# POWERSYSTEM.net
KiCad netlist of a schematic drawn in Altium Designer
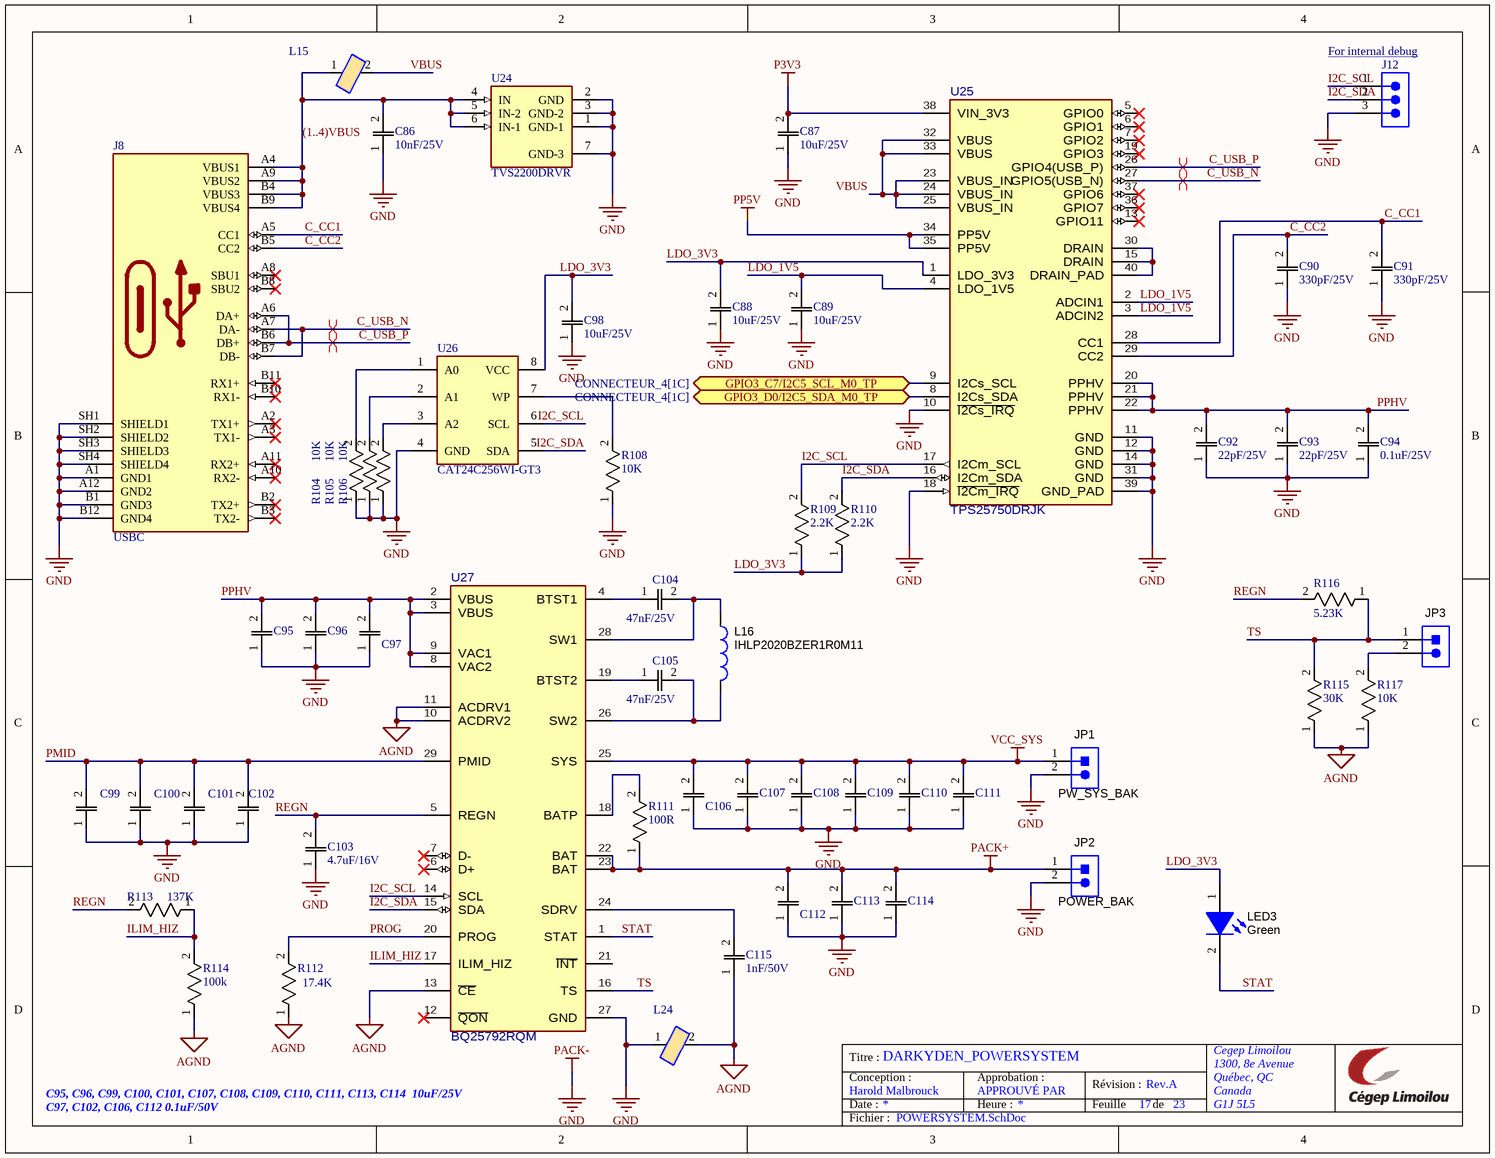
[diagram p0: POWERSYSTEM.SchDoc]

(export (version "E")
  (design (tool "Eeschema 10.0.6"))
  (components
    (comp (ref "C86")
      (value "10nF/25V")
      (footprint "C0805")
      (description "0.01uF 25V X7R 10% SMD 0805 125C Paper T/R")
      (fields
        (field (name "MANUFACTURER_PART_NUMBER") "C0805C103K3RACTU")
        (field (name "MOUSER PART NUMBER") "80-C0805C103K3R")
      )
      (libsource (lib "DARKYDEN") (part "C0805C103K3RACTU"))
    )
    (comp (ref "C87")
      (value "10uF/25V")
      (footprint "C0805")
      (description "10uF / 25 VDC, +85degC, X5R Dielec, +/-10% ¦ KEMET C0805C106K3PACTU 0805")
      (fields
        (field (name "MANUFACTURER") "KEMET")
        (field (name "MANUFACTURER PART NUMBER") "C0805C106K3PACTU")
      )
      (libsource (lib "DARKYDEN") (part "C0805C106K3PACTU"))
    )
    (comp (ref "C88")
      (value "10uF/25V")
      (footprint "C0805")
      (description "10uF / 25 VDC, +85degC, X5R Dielec, +/-10% ¦ KEMET C0805C106K3PACTU 0805")
      (fields
        (field (name "MANUFACTURER") "KEMET")
        (field (name "MANUFACTURER PART NUMBER") "C0805C106K3PACTU")
      )
      (libsource (lib "DARKYDEN") (part "C0805C106K3PACTU"))
    )
    (comp (ref "C89")
      (value "10uF/25V")
      (footprint "C0805")
      (description "10uF / 25 VDC, +85degC, X5R Dielec, +/-10% ¦ KEMET C0805C106K3PACTU 0805")
      (fields
        (field (name "MANUFACTURER") "KEMET")
        (field (name "MANUFACTURER PART NUMBER") "C0805C106K3PACTU")
      )
      (libsource (lib "DARKYDEN") (part "C0805C106K3PACTU"))
    )
    (comp (ref "C90")
      (value "330pF/25V")
      (footprint "SamacSys:C0805")
      (description "330pF 25VC0G 0805 10%")
      (fields
        (field (name "MANUFACTURER_PART_NUMBER") "C0805C331K3GACTU")
        (field (name "MOUSER PART NUMBER") "80-C0805C331K3G")
      )
      (libsource (lib "DARKYDEN") (part "C0805C331K3GACTU"))
    )
    (comp (ref "C91")
      (value "330pF/25V")
      (footprint "SamacSys:C0805")
      (description "330pF 25VC0G 0805 10%")
      (fields
        (field (name "MANUFACTURER_PART_NUMBER") "C0805C331K3GACTU")
        (field (name "MOUSER PART NUMBER") "80-C0805C331K3G")
      )
      (libsource (lib "DARKYDEN") (part "C0805C331K3GACTU"))
    )
    (comp (ref "C92")
      (value "22pF/25V")
      (footprint "c0805")
      (description "22uF/25V 20% X5R 0805")
      (fields
        (field (name "MANUFACTURER_PART_NUMBER") "CL21A226MAYNNNE")
        (field (name "MOUSER PART NUMBER") "187-CL21A226MAYNNNE")
      )
      (libsource (lib "DARKYDEN") (part "CL21A226MAYNNNE"))
    )
    (comp (ref "C93")
      (value "22pF/25V")
      (footprint "c0805")
      (description "22uF/25V 20% X5R 0805")
      (fields
        (field (name "MANUFACTURER_PART_NUMBER") "CL21A226MAYNNNE")
        (field (name "MOUSER PART NUMBER") "187-CL21A226MAYNNNE")
      )
      (libsource (lib "DARKYDEN") (part "CL21A226MAYNNNE"))
    )
    (comp (ref "C94")
      (value "0.1uF/25V")
      (footprint "c0805")
      (description "0.1uF 25V X7R 10% SMD 0805 125C Plastic T/R")
      (fields
        (field (name "MANUFACTURER") "KEMET")
        (field (name "MANUFACTURER PART NUMBER") "C0805C104K3RACTU")
      )
      (libsource (lib "DARKYDEN") (part "C0805C104K3RACTU"))
    )
    (comp (ref "C95")
      (value "10uF/25V")
      (footprint "C0805")
      (description "10uF / 25 VDC, +85degC, X5R Dielec, +/-10% ¦ KEMET C0805C106K3PACTU 0805")
      (fields
        (field (name "MANUFACTURER") "KEMET")
        (field (name "MANUFACTURER PART NUMBER") "C0805C106K3PACTU")
      )
      (libsource (lib "DARKYDEN") (part "C0805C106K3PACTU"))
    )
    (comp (ref "C96")
      (value "10uF/25V")
      (footprint "C0805")
      (description "10uF / 25 VDC, +85degC, X5R Dielec, +/-10% ¦ KEMET C0805C106K3PACTU 0805")
      (fields
        (field (name "MANUFACTURER") "KEMET")
        (field (name "MANUFACTURER PART NUMBER") "C0805C106K3PACTU")
      )
      (libsource (lib "DARKYDEN") (part "C0805C106K3PACTU"))
    )
    (comp (ref "C97")
      (value "0.1uF/50V")
      (footprint "C0805")
      (description "0.1uF/50V X7R 10% 0805 Multilayer Ceramic Capacitors Mlcc Smd/Smt Rohs")
      (fields
        (field (name "MANUFACTURER_PART_NUMBER") "C0805C104K5RACTU")
        (field (name "MOUSER PART NUMBER") "80-C0805C104K5R")
      )
      (libsource (lib "DARKYDEN") (part "C0805C104K5RACTU"))
    )
    (comp (ref "C98")
      (value "10uF/25V")
      (footprint "C0805")
      (description "10uF / 25 VDC, +85degC, X5R Dielec, +/-10% ¦ KEMET C0805C106K3PACTU 0805")
      (fields
        (field (name "MANUFACTURER") "KEMET")
        (field (name "MANUFACTURER PART NUMBER") "C0805C106K3PACTU")
      )
      (libsource (lib "DARKYDEN") (part "C0805C106K3PACTU"))
    )
    (comp (ref "C99")
      (value "10uF/25V")
      (footprint "C0805")
      (description "10uF / 25 VDC, +85degC, X5R Dielec, +/-10% ¦ KEMET C0805C106K3PACTU 0805")
      (fields
        (field (name "MANUFACTURER") "KEMET")
        (field (name "MANUFACTURER PART NUMBER") "C0805C106K3PACTU")
      )
      (libsource (lib "DARKYDEN") (part "C0805C106K3PACTU"))
    )
    (comp (ref "C100")
      (value "10uF/25V")
      (footprint "C0805")
      (description "10uF / 25 VDC, +85degC, X5R Dielec, +/-10% ¦ KEMET C0805C106K3PACTU 0805")
      (fields
        (field (name "MANUFACTURER") "KEMET")
        (field (name "MANUFACTURER PART NUMBER") "C0805C106K3PACTU")
      )
      (libsource (lib "DARKYDEN") (part "C0805C106K3PACTU"))
    )
    (comp (ref "C101")
      (value "10uF/25V")
      (footprint "C0805")
      (description "10uF / 25 VDC, +85degC, X5R Dielec, +/-10% ¦ KEMET C0805C106K3PACTU 0805")
      (fields
        (field (name "MANUFACTURER") "KEMET")
        (field (name "MANUFACTURER PART NUMBER") "C0805C106K3PACTU")
      )
      (libsource (lib "DARKYDEN") (part "C0805C106K3PACTU"))
    )
    (comp (ref "C102")
      (value "0.1uF/50V")
      (footprint "C0805")
      (description "0.1uF/50V X7R 10% 0805 Multilayer Ceramic Capacitors Mlcc Smd/Smt Rohs")
      (fields
        (field (name "MANUFACTURER_PART_NUMBER") "C0805C104K5RACTU")
        (field (name "MOUSER PART NUMBER") "80-C0805C104K5R")
      )
      (libsource (lib "DARKYDEN") (part "C0805C104K5RACTU"))
    )
    (comp (ref "C103")
      (value "4.7uF/16V")
      (footprint "C0805")
      (description "4.7 uF, 16 V, ± 10%, X7R, 0805 [2012 Metric]")
      (fields
        (field (name "MANUFACTURER_PART_NUMBER") "C0805C475K4RACTU")
        (field (name "MOUSER PART NUMBER") "80-C0805C475K4R")
      )
      (libsource (lib "DARKYDEN") (part "C0805C475K4RACTU"))
    )
    (comp (ref "C104")
      (value "47nF/25V")
      (footprint "C0805")
      (description "47nF/25V C0G 10% Pad SMD 0805 125C Extreme Low ESR T/R")
      (fields
        (field (name "MANUFACTURER_PART_NUMBER") "C0805C473K3GACTU")
        (field (name "MOUSER PART NUMBER") "80-C0805C473K3G")
      )
      (libsource (lib "DARKYDEN") (part "C0805C473K3GACTU"))
    )
    (comp (ref "C105")
      (value "47nF/25V")
      (footprint "C0805")
      (description "47nF/25V C0G 10% Pad SMD 0805 125C Extreme Low ESR T/R")
      (fields
        (field (name "MANUFACTURER_PART_NUMBER") "C0805C473K3GACTU")
        (field (name "MOUSER PART NUMBER") "80-C0805C473K3G")
      )
      (libsource (lib "DARKYDEN") (part "C0805C473K3GACTU"))
    )
    (comp (ref "C106")
      (value "0.1uF/50V")
      (footprint "C0805")
      (description "0.1uF/50V X7R 10% 0805 Multilayer Ceramic Capacitors Mlcc Smd/Smt Rohs")
      (fields
        (field (name "MANUFACTURER_PART_NUMBER") "C0805C104K5RACTU")
        (field (name "MOUSER PART NUMBER") "80-C0805C104K5R")
      )
      (libsource (lib "DARKYDEN") (part "C0805C104K5RACTU"))
    )
    (comp (ref "C107")
      (value "10uF/25V")
      (footprint "C0805")
      (description "10uF / 25 VDC, +85degC, X5R Dielec, +/-10% ¦ KEMET C0805C106K3PACTU 0805")
      (fields
        (field (name "MANUFACTURER") "KEMET")
        (field (name "MANUFACTURER PART NUMBER") "C0805C106K3PACTU")
      )
      (libsource (lib "DARKYDEN") (part "C0805C106K3PACTU"))
    )
    (comp (ref "C108")
      (value "10uF/25V")
      (footprint "C0805")
      (description "10uF / 25 VDC, +85degC, X5R Dielec, +/-10% ¦ KEMET C0805C106K3PACTU 0805")
      (fields
        (field (name "MANUFACTURER") "KEMET")
        (field (name "MANUFACTURER PART NUMBER") "C0805C106K3PACTU")
      )
      (libsource (lib "DARKYDEN") (part "C0805C106K3PACTU"))
    )
    (comp (ref "C109")
      (value "10uF/25V")
      (footprint "C0805")
      (description "10uF / 25 VDC, +85degC, X5R Dielec, +/-10% ¦ KEMET C0805C106K3PACTU 0805")
      (fields
        (field (name "MANUFACTURER") "KEMET")
        (field (name "MANUFACTURER PART NUMBER") "C0805C106K3PACTU")
      )
      (libsource (lib "DARKYDEN") (part "C0805C106K3PACTU"))
    )
    (comp (ref "C110")
      (value "10uF/25V")
      (footprint "C0805")
      (description "10uF / 25 VDC, +85degC, X5R Dielec, +/-10% ¦ KEMET C0805C106K3PACTU 0805")
      (fields
        (field (name "MANUFACTURER") "KEMET")
        (field (name "MANUFACTURER PART NUMBER") "C0805C106K3PACTU")
      )
      (libsource (lib "DARKYDEN") (part "C0805C106K3PACTU"))
    )
    (comp (ref "C111")
      (value "10uF/25V")
      (footprint "C0805")
      (description "10uF / 25 VDC, +85degC, X5R Dielec, +/-10% ¦ KEMET C0805C106K3PACTU 0805")
      (fields
        (field (name "MANUFACTURER") "KEMET")
        (field (name "MANUFACTURER PART NUMBER") "C0805C106K3PACTU")
      )
      (libsource (lib "DARKYDEN") (part "C0805C106K3PACTU"))
    )
    (comp (ref "C112")
      (value "0.1uF/50V")
      (footprint "C0805")
      (description "0.1uF/50V X7R 10% 0805 Multilayer Ceramic Capacitors Mlcc Smd/Smt Rohs")
      (fields
        (field (name "MANUFACTURER_PART_NUMBER") "C0805C104K5RACTU")
        (field (name "MOUSER PART NUMBER") "80-C0805C104K5R")
      )
      (libsource (lib "DARKYDEN") (part "C0805C104K5RACTU"))
    )
    (comp (ref "C113")
      (value "10uF/25V")
      (footprint "C0805")
      (description "10uF / 25 VDC, +85degC, X5R Dielec, +/-10% ¦ KEMET C0805C106K3PACTU 0805")
      (fields
        (field (name "MANUFACTURER") "KEMET")
        (field (name "MANUFACTURER PART NUMBER") "C0805C106K3PACTU")
      )
      (libsource (lib "DARKYDEN") (part "C0805C106K3PACTU"))
    )
    (comp (ref "C114")
      (value "10uF/25V")
      (footprint "C0805")
      (description "10uF / 25 VDC, +85degC, X5R Dielec, +/-10% ¦ KEMET C0805C106K3PACTU 0805")
      (fields
        (field (name "MANUFACTURER") "KEMET")
        (field (name "MANUFACTURER PART NUMBER") "C0805C106K3PACTU")
      )
      (libsource (lib "DARKYDEN") (part "C0805C106K3PACTU"))
    )
    (comp (ref "C115")
      (value "1nF/50V")
      (footprint "C0805")
      (description "Multilayer Ceramic Capacitor 1000 Pf 50 V ½ 10% X7R 0805 [2012 Metric]")
      (fields
        (field (name "MANUFACTURER_PART_NUMBER") "C0805C102K5RAC-TU")
        (field (name "MANUFACTURER") "KEMET")
      )
      (libsource (lib "DARKYDEN") (part "C0805C102K5RACTU"))
    )
    (comp (ref "J8")
      (value "USBC")
      (footprint "USB_C")
      (fields (field (name "MF") "Molex") (field (name "MP") "2012670005"))
      (libsource (lib "DARKYDEN") (part "USBC"))
    )
    (comp (ref "J12")
      (value "61300311121")
      (footprint "61300311121")
      (description "WR-PHD Pin Header, THT, Vertical, pitch 2.54mm, 1 Row, 3P")
      (fields (field (name "MANUFACTURER") "Wurth Elektronik"))
      (libsource (lib "Header") (part "61300311121"))
    )
    (comp (ref "JP1")
      (value "PW_SYS_BAK")
      (footprint "61300211121")
      (description "Header, 100mil, 2x1, Tin, TH")
      (fields
        (field (name "PARTNUMBER") "PEC02SAAN")
        (field (name "MANUFACTURER") "Sullins Connector Solutions")
        (field (name "PUBLISHER") "Texas Instruments")
      )
      (libsource (lib "texas_instrument_power") (part "Header_2x1"))
    )
    (comp (ref "JP2")
      (value "POWER_BAK")
      (footprint "61300211121")
      (description "Header, 100mil, 2x1, Tin, TH")
      (fields
        (field (name "PARTNUMBER") "PEC02SAAN")
        (field (name "MANUFACTURER") "Sullins Connector Solutions")
        (field (name "PUBLISHER") "Texas Instruments")
      )
      (libsource (lib "texas_instrument_power") (part "Header_2x1"))
    )
    (comp (ref "JP3")
      (value "TS")
      (footprint "61300211121")
      (description "Header, 100mil, 2x1, Tin, TH")
      (fields
        (field (name "PARTNUMBER") "PEC02SAAN")
        (field (name "MANUFACTURER") "Sullins Connector Solutions")
        (field (name "PUBLISHER") "Texas Instruments")
      )
      (libsource (lib "texas_instrument_power") (part "Header_2x1"))
    )
    (comp (ref "L15")
      (value "FBMJ2125HM210NT")
      (footprint "INDC2012X105N")
      (description "Ferrite Beads Power Chip 21Ohm 30% 100MHz 6A 0.004Ohm DCR 0805 Automotive T/R")
      (fields
        (field (name "MANUFACTURER") "Taiyo Yuden")
        (field (name "MOUSER PART NUMBER") "963-FBMJ2125HM210NT")
      )
      (libsource (lib "SamacSys") (part "FBMJ2125HM210NT"))
    )
    (comp (ref "L16")
      (value "IHLP2020BZER1R0M11")
      (footprint "IHLP-2020BZ")
      (description "Inductor, Shielded Drum Core, Powdered Iron, 1 uH, 7 A, 0.0181 ohm, SMD")
      (fields (field (name "MANUFACTURER") "Vishay-Dale") (field (name "PUBLISHER") "Texas Instruments"))
      (libsource (lib "texas_instrument_power") (part "IHLP2020BZER1R0M11"))
    )
    (comp (ref "L24")
      (value "FBMJ2125HM210NT")
      (footprint "INDC2012X105N")
      (description "Ferrite Beads Power Chip 21Ohm 30% 100MHz 6A 0.004Ohm DCR 0805 Automotive T/R")
      (fields
        (field (name "MANUFACTURER") "Taiyo Yuden")
        (field (name "MOUSER PART NUMBER") "963-FBMJ2125HM210NT")
      )
      (libsource (lib "SamacSys") (part "FBMJ2125HM210NT"))
    )
    (comp (ref "LED3")
      (value "Green")
      (footprint "LED_LTST-C190")
      (description "LED, Green, SMD")
      (fields (field (name "MANUFACTURER") "Lite-On") (field (name "PARTNUMBER") "LTST-C190GKT"))
      (libsource (lib "PD_BQ_Ref_Design") (part "LED_Gr_SMD"))
    )
    (comp (ref "R104")
      (value "10K")
      (footprint "SamacSys:RESC1608X55N")
      (description "10K Ohm 5% Res Thick Film 0603  0.1W(1/10W) ±200ppm/C Pad SMD Automotive T/R")
      (fields
        (field (name "MANUFACTURER_PART_NUMBER") "ERJ-3GEYJ103V")
        (field (name "MOUSER PART NUMBER") "667-ERJ-3GEYJ103V")
      )
      (libsource (lib "DARKYDEN") (part "ERJ-3GEYJ103V"))
    )
    (comp (ref "R105")
      (value "10K")
      (footprint "SamacSys:RESC1608X55N")
      (description "10K Ohm 5% Res Thick Film 0603  0.1W(1/10W) ±200ppm/C Pad SMD Automotive T/R")
      (fields
        (field (name "MANUFACTURER_PART_NUMBER") "ERJ-3GEYJ103V")
        (field (name "MOUSER PART NUMBER") "667-ERJ-3GEYJ103V")
      )
      (libsource (lib "DARKYDEN") (part "ERJ-3GEYJ103V"))
    )
    (comp (ref "R106")
      (value "10K")
      (footprint "SamacSys:RESC1608X55N")
      (description "10K Ohm 5% Res Thick Film 0603  0.1W(1/10W) ±200ppm/C Pad SMD Automotive T/R")
      (fields
        (field (name "MANUFACTURER_PART_NUMBER") "ERJ-3GEYJ103V")
        (field (name "MOUSER PART NUMBER") "667-ERJ-3GEYJ103V")
      )
      (libsource (lib "DARKYDEN") (part "ERJ-3GEYJ103V"))
    )
    (comp (ref "R108")
      (value "10K")
      (footprint "SamacSys:RESC1608X55N")
      (description "10K Ohm 5% Res Thick Film 0603  0.1W(1/10W) ±200ppm/C Pad SMD Automotive T/R")
      (fields
        (field (name "MANUFACTURER_PART_NUMBER") "ERJ-3GEYJ103V")
        (field (name "MOUSER PART NUMBER") "667-ERJ-3GEYJ103V")
      )
      (libsource (lib "DARKYDEN") (part "ERJ-3GEYJ103V"))
    )
    (comp (ref "R109")
      (value "2.2K")
      (footprint "SamacSys:RESC1608X55N")
      (description "2.2 kOhm, ï¿½ 5%, 100 mW, 0603 [1608 Metric], Thick Film, General Purpose")
      (fields
        (field (name "MANUFACTURER_PART_NUMBER") "ERJ-3GEYJ222V")
        (field (name "MOUSER PART NUMBER") "667-ERJ-3GEYJ222V")
      )
      (libsource (lib "DARKYDEN") (part "ERJ-3GEYJ222V"))
    )
    (comp (ref "R110")
      (value "2.2K")
      (footprint "SamacSys:RESC1608X55N")
      (description "2.2 kOhm, ï¿½ 5%, 100 mW, 0603 [1608 Metric], Thick Film, General Purpose")
      (fields
        (field (name "MANUFACTURER_PART_NUMBER") "ERJ-3GEYJ222V")
        (field (name "MOUSER PART NUMBER") "667-ERJ-3GEYJ222V")
      )
      (libsource (lib "DARKYDEN") (part "ERJ-3GEYJ222V"))
    )
    (comp (ref "R111")
      (value "100R")
      (footprint "SamacSys:RESC1608X55N")
      (description "100 Ohm 1% 1/10W 0603 ±100ppm/°C Molded SMD Punched Carrier T/R")
      (fields
        (field (name "MANUFACTURER_PART_NUMBER") "ERJ-3EKF1000V")
        (field (name "MOUSER PART NUMBER") "667-ERJ-3EKF1000V")
      )
      (libsource (lib "DARKYDEN") (part "ERJ-3EKF1000V"))
    )
    (comp (ref "R112")
      (value "17.4K")
      (footprint "SamacSys:RESC1608X55N")
      (description "17.4K Ohm 1% 1/10W +/-100ppm/ßC Molded Res Thick Film 0603  SMD Punched Carrier T/R")
      (fields
        (field (name "MANUFACTURER_PART_NUMBER") "ERJ-3EKF1742V")
        (field (name "MOUSER PART NUMBER") "667-ERJ-3EKF1742V")
      )
      (libsource (lib "DARKYDEN") (part "ERJ-3EKF1742V"))
    )
    (comp (ref "R113")
      (value "137K")
      (footprint "SamacSys:RESC1608X55N")
      (description "137K Ohm 1% 1/10W Res Thick Film 0603 ±100ppm/°C SMD Punched Carrier T/R")
      (fields
        (field (name "MANUFACTURER_PART_NUMBER") "ERJ-3EKF1373V")
        (field (name "MOUSER PART NUMBER") "667-ERJ-3EKF1373V")
      )
      (libsource (lib "DARKYDEN") (part "ERJ-3EKF1373V"))
    )
    (comp (ref "R114")
      (value "100k")
      (footprint "SamacSys:RESC1608X55N")
      (description "100K Ohm 5%  Res Thick Film 0603 1/10W +/-200ppm/ßC Molded SMD Punched Carrier T/R")
      (fields
        (field (name "MANUFACTURER_PART_NUMBER") "ERJ-3GEYJ104V")
        (field (name "MOUSER PART NUMBER") "667-ERJ-3GEYJ104V")
      )
      (libsource (lib "DARKYDEN") (part "ERJ-3GEYJ104V"))
    )
    (comp (ref "R115")
      (value "30K")
      (footprint "SamacSys:RESC1608X55N")
      (description "30K Ohm 5% 0.1W(1/10W) +/-200ppm/ßC Res Thick Film 0603  SMD Automotive T/R")
      (fields
        (field (name "MANUFACTURER_PART_NUMBER") "ERJ-3GEYJ303V")
        (field (name "MOUSER PART NUMBER") "667-ERJ-3GEYJ303V")
      )
      (libsource (lib "DARKYDEN") (part "ERJ-3GEYJ303V"))
    )
    (comp (ref "R116")
      (value "5.23K")
      (footprint "SamacSys:RESC1608X55N")
      (description "5.23K Ohm 1% 1/10W Res Thick Film 0603+/-100ppm/ßC Molded SMD Punched Carrier T/R")
      (fields
        (field (name "MANUFACTURER_PART_NUMBER") "ERJ-3EKF5231V")
        (field (name "MOUSER PART NUMBER") "667-ERJ-3EKF5231V")
      )
      (libsource (lib "DARKYDEN") (part "ERJ-3EKF5231V"))
    )
    (comp (ref "R117")
      (value "10K")
      (footprint "SamacSys:RESC1608X55N")
      (description "10K Ohm 5% Res Thick Film 0603  0.1W(1/10W) ±200ppm/C Pad SMD Automotive T/R")
      (fields
        (field (name "MANUFACTURER_PART_NUMBER") "ERJ-3GEYJ103V")
        (field (name "MOUSER PART NUMBER") "667-ERJ-3GEYJ103V")
      )
      (libsource (lib "DARKYDEN") (part "ERJ-3GEYJ103V"))
    )
    (comp (ref "U24")
      (value "TVS2200DRVR")
      (footprint "SON65P200X200X80-7N")
      (description "ESD Suppressors / TVS Diodes 22V flat-clamp surge protection device 6-WSON -40 to 125")
      (fields (field (name "MF") "Texas Instruments"))
      (libsource (lib "TVS2200") (part "TVS2200DRVR"))
    )
    (comp (ref "U25")
      (value "TPS25750DRJK")
      (footprint "RJK0038B-C01-MFG")
      (description "USB Type-C and USB PD Controller with Integrated Power Switches Optimized for Power Applications")
      (fields (field (name "MANUFACTURER") "Texas Instruments"))
      (libsource (lib "PD_BQ_Ref_Design") (part "TPS25750DRJK"))
    )
    (comp (ref "U26")
      (value "CAT24C256WI-GT3")
      (footprint "SOIC127P600X175-8N")
      (description "EEPROM Memory IC 256Kbit I2C 1 MHz 500 ns 8-SOIC")
      (fields (field (name "MOUSER PART NUMBER") "698-CAT24C256WI-GT3"))
      (libsource (lib "SamacSys") (part "CAT24C256WI-GT3"))
    )
    (comp (ref "U27")
      (value "BQ25792RQM")
      (footprint "RQM0029A-MFG")
      (description "BQ2579x HotRod")
      (fields (field (name "MANUFACTURER") "Texas Instruments"))
      (libsource (lib "PD_BQ_Ref_Design") (part "BQ2579x"))
    )
  )
  (nets
    (net (code "1") (name "/(1..4)VBUS") (class "Default")
      (node (ref "C86") (pin "2") (pinfunction "2_2") (pintype "passive"))
      (node (ref "J8") (pin "A4") (pinfunction "VBUS1_A4") (pintype "power_in"))
      (node (ref "J8") (pin "A9") (pinfunction "VBUS2_A9") (pintype "power_in"))
      (node (ref "J8") (pin "B4") (pinfunction "VBUS3_B4") (pintype "power_in"))
      (node (ref "J8") (pin "B9") (pinfunction "VBUS4_B9") (pintype "power_in"))
      (node (ref "L15") (pin "1") (pinfunction "1_1") (pintype "passive"))
      (node (ref "U24") (pin "4") (pinfunction "IN_4") (pintype "input"))
      (node (ref "U24") (pin "5") (pinfunction "IN-2_5") (pintype "input"))
      (node (ref "U24") (pin "6") (pinfunction "IN-1_6") (pintype "input"))
    )
    (net (code "2") (name "/C_CC1") (class "Default")
      (node (ref "C91") (pin "2") (pinfunction "2_2") (pintype "passive"))
      (node (ref "J8") (pin "A5") (pinfunction "CC1_A5") (pintype "bidirectional"))
      (node (ref "U25") (pin "28") (pinfunction "CC1_28") (pintype "passive"))
    )
    (net (code "3") (name "/C_CC2") (class "Default")
      (node (ref "C90") (pin "2") (pinfunction "2_2") (pintype "passive"))
      (node (ref "J8") (pin "B5") (pinfunction "CC2_B5") (pintype "bidirectional"))
      (node (ref "U25") (pin "29") (pinfunction "CC2_29") (pintype "passive"))
    )
    (net (code "4") (name "/C_USB_N") (class "Default")
      (node (ref "J8") (pin "A7") (pinfunction "DA-_A7") (pintype "bidirectional"))
      (node (ref "J8") (pin "B7") (pinfunction "DB-_B7") (pintype "bidirectional"))
      (node (ref "U25") (pin "27") (pinfunction "GPIO5(USB_N)_27") (pintype "bidirectional"))
    )
    (net (code "5") (name "/C_USB_P") (class "Default")
      (node (ref "J8") (pin "A6") (pinfunction "DA+_A6") (pintype "bidirectional"))
      (node (ref "J8") (pin "B6") (pinfunction "DB+_B6") (pintype "bidirectional"))
      (node (ref "U25") (pin "26") (pinfunction "GPIO4(USB_P)_26") (pintype "bidirectional"))
    )
    (net (code "6") (name "/GPIO3_C7{slash}I2C5_SCL_M0_TP") (class "Default")
      (node (ref "U25") (pin "9") (pinfunction "I2Cs_SCL_9") (pintype "passive"))
    )
    (net (code "7") (name "/GPIO3_D0{slash}I2C5_SDA_M0_TP") (class "Default")
      (node (ref "U25") (pin "8") (pinfunction "I2Cs_SDA_8") (pintype "passive"))
    )
    (net (code "8") (name "/I2C_SCL") (class "Default")
      (node (ref "J12") (pin "1") (pinfunction "1_1") (pintype "passive"))
      (node (ref "R109") (pin "2") (pinfunction "2_2") (pintype "passive"))
      (node (ref "U25") (pin "17") (pinfunction "I2Cm_SCL_17") (pintype "output"))
      (node (ref "U26") (pin "6") (pinfunction "SCL_6") (pintype "passive"))
      (node (ref "U27") (pin "14") (pinfunction "SCL_14") (pintype "input"))
    )
    (net (code "9") (name "/I2C_SDA") (class "Default")
      (node (ref "J12") (pin "2") (pinfunction "2_2") (pintype "passive"))
      (node (ref "R110") (pin "2") (pinfunction "2_2") (pintype "passive"))
      (node (ref "U25") (pin "16") (pinfunction "I2Cm_SDA_16") (pintype "bidirectional"))
      (node (ref "U26") (pin "5") (pinfunction "SDA_5") (pintype "passive"))
      (node (ref "U27") (pin "15") (pinfunction "SDA_15") (pintype "bidirectional"))
    )
    (net (code "10") (name "/ILIM_HIZ") (class "Default")
      (node (ref "R113") (pin "1") (pinfunction "1_1") (pintype "passive"))
      (node (ref "R114") (pin "2") (pinfunction "2_2") (pintype "passive"))
      (node (ref "U27") (pin "17") (pinfunction "ILIM_HIZ_17") (pintype "passive"))
    )
    (net (code "11") (name "/LDO_1V5") (class "Default")
      (node (ref "C89") (pin "2") (pinfunction "2_2") (pintype "passive"))
      (node (ref "U25") (pin "2") (pinfunction "ADCIN1_2") (pintype "passive"))
      (node (ref "U25") (pin "3") (pinfunction "ADCIN2_3") (pintype "passive"))
      (node (ref "U25") (pin "4") (pinfunction "LDO_1V5_4") (pintype "passive"))
    )
    (net (code "12") (name "/LDO_3V3") (class "Default")
      (node (ref "C88") (pin "2") (pinfunction "2_2") (pintype "passive"))
      (node (ref "C98") (pin "2") (pinfunction "2_2") (pintype "passive"))
      (node (ref "LED3") (pin "1") (pinfunction "A_1") (pintype "passive"))
      (node (ref "R109") (pin "1") (pinfunction "1_1") (pintype "passive"))
      (node (ref "R110") (pin "1") (pinfunction "1_1") (pintype "passive"))
      (node (ref "U25") (pin "1") (pinfunction "LDO_3V3_1") (pintype "passive"))
      (node (ref "U26") (pin "8") (pinfunction "VCC_8") (pintype "passive"))
    )
    (net (code "13") (name "/PMID") (class "Default")
      (node (ref "C100") (pin "2") (pinfunction "2_2") (pintype "passive"))
      (node (ref "C101") (pin "2") (pinfunction "2_2") (pintype "passive"))
      (node (ref "C102") (pin "2") (pinfunction "2_2") (pintype "passive"))
      (node (ref "C99") (pin "2") (pinfunction "2_2") (pintype "passive"))
      (node (ref "U27") (pin "29") (pinfunction "PMID_29") (pintype "passive"))
    )
    (net (code "14") (name "/PPHV") (class "Default")
      (node (ref "C92") (pin "2") (pinfunction "2_2") (pintype "passive"))
      (node (ref "C93") (pin "2") (pinfunction "2_2") (pintype "passive"))
      (node (ref "C94") (pin "2") (pinfunction "2_2") (pintype "passive"))
      (node (ref "C95") (pin "2") (pinfunction "2_2") (pintype "passive"))
      (node (ref "C96") (pin "2") (pinfunction "2_2") (pintype "passive"))
      (node (ref "C97") (pin "2") (pinfunction "2_2") (pintype "passive"))
      (node (ref "U25") (pin "20") (pinfunction "PPHV_20") (pintype "passive"))
      (node (ref "U25") (pin "21") (pinfunction "PPHV_21") (pintype "passive"))
      (node (ref "U25") (pin "22") (pinfunction "PPHV_22") (pintype "passive"))
      (node (ref "U27") (pin "2") (pinfunction "VBUS_2") (pintype "power_in"))
      (node (ref "U27") (pin "3") (pinfunction "VBUS_3") (pintype "power_in"))
      (node (ref "U27") (pin "8") (pinfunction "VAC2_8") (pintype "power_in"))
      (node (ref "U27") (pin "9") (pinfunction "VAC1_9") (pintype "power_in"))
    )
    (net (code "15") (name "/PROG") (class "Default")
      (node (ref "R112") (pin "2") (pinfunction "2_2") (pintype "passive"))
      (node (ref "U27") (pin "20") (pinfunction "PROG_20") (pintype "passive"))
    )
    (net (code "16") (name "/REGN") (class "Default")
      (node (ref "C103") (pin "2") (pinfunction "2_2") (pintype "passive"))
      (node (ref "R113") (pin "2") (pinfunction "2_2") (pintype "passive"))
      (node (ref "R116") (pin "2") (pinfunction "2_2") (pintype "passive"))
      (node (ref "U27") (pin "5") (pinfunction "REGN_5") (pintype "passive"))
    )
    (net (code "17") (name "/STAT") (class "Default")
      (node (ref "LED3") (pin "2") (pinfunction "K_2") (pintype "passive"))
      (node (ref "U27") (pin "1") (pinfunction "STAT_1") (pintype "passive"))
    )
    (net (code "18") (name "/TS") (class "Default")
      (node (ref "JP3") (pin "1") (pinfunction "1_1") (pintype "passive"))
      (node (ref "R115") (pin "2") (pinfunction "2_2") (pintype "passive"))
      (node (ref "R116") (pin "1") (pinfunction "1_1") (pintype "passive"))
      (node (ref "U27") (pin "16") (pinfunction "TS_16") (pintype "passive"))
    )
    (net (code "19") (name "/VBUS") (class "Default")
      (node (ref "L15") (pin "2") (pinfunction "2_2") (pintype "passive"))
      (node (ref "U25") (pin "23") (pinfunction "VBUS_IN_23") (pintype "power_in"))
      (node (ref "U25") (pin "24") (pinfunction "VBUS_IN_24") (pintype "power_in"))
      (node (ref "U25") (pin "25") (pinfunction "VBUS_IN_25") (pintype "power_in"))
      (node (ref "U25") (pin "32") (pinfunction "VBUS_32") (pintype "power_in"))
      (node (ref "U25") (pin "33") (pinfunction "VBUS_33") (pintype "power_in"))
    )
    (net (code "20") (name "AGND") (class "Default")
      (node (ref "C115") (pin "1") (pinfunction "1_1") (pintype "passive"))
      (node (ref "L24") (pin "2") (pinfunction "2_2") (pintype "passive"))
      (node (ref "R112") (pin "1") (pinfunction "1_1") (pintype "passive"))
      (node (ref "R114") (pin "1") (pinfunction "1_1") (pintype "passive"))
      (node (ref "R115") (pin "1") (pinfunction "1_1") (pintype "passive"))
      (node (ref "R117") (pin "1") (pinfunction "1_1") (pintype "passive"))
      (node (ref "U27") (pin "10") (pinfunction "ACDRV2_10") (pintype "power_in"))
      (node (ref "U27") (pin "11") (pinfunction "ACDRV1_11") (pintype "power_in"))
      (node (ref "U27") (pin "13") (pinfunction "~{CE}_13") (pintype "passive"))
    )
    (net (code "21") (name "GND") (class "Default")
      (node (ref "C100") (pin "1") (pinfunction "1_1") (pintype "passive"))
      (node (ref "C101") (pin "1") (pinfunction "1_1") (pintype "passive"))
      (node (ref "C102") (pin "1") (pinfunction "1_1") (pintype "passive"))
      (node (ref "C103") (pin "1") (pinfunction "1_1") (pintype "passive"))
      (node (ref "C106") (pin "1") (pinfunction "1_1") (pintype "passive"))
      (node (ref "C107") (pin "1") (pinfunction "1_1") (pintype "passive"))
      (node (ref "C108") (pin "1") (pinfunction "1_1") (pintype "passive"))
      (node (ref "C109") (pin "1") (pinfunction "1_1") (pintype "passive"))
      (node (ref "C110") (pin "1") (pinfunction "1_1") (pintype "passive"))
      (node (ref "C111") (pin "1") (pinfunction "1_1") (pintype "passive"))
      (node (ref "C112") (pin "1") (pinfunction "1_1") (pintype "passive"))
      (node (ref "C113") (pin "1") (pinfunction "1_1") (pintype "passive"))
      (node (ref "C114") (pin "1") (pinfunction "1_1") (pintype "passive"))
      (node (ref "C86") (pin "1") (pinfunction "1_1") (pintype "passive"))
      (node (ref "C87") (pin "1") (pinfunction "1_1") (pintype "passive"))
      (node (ref "C88") (pin "1") (pinfunction "1_1") (pintype "passive"))
      (node (ref "C89") (pin "1") (pinfunction "1_1") (pintype "passive"))
      (node (ref "C90") (pin "1") (pinfunction "1_1") (pintype "passive"))
      (node (ref "C91") (pin "1") (pinfunction "1_1") (pintype "passive"))
      (node (ref "C92") (pin "1") (pinfunction "1_1") (pintype "passive"))
      (node (ref "C93") (pin "1") (pinfunction "1_1") (pintype "passive"))
      (node (ref "C94") (pin "1") (pinfunction "1_1") (pintype "passive"))
      (node (ref "C95") (pin "1") (pinfunction "1_1") (pintype "passive"))
      (node (ref "C96") (pin "1") (pinfunction "1_1") (pintype "passive"))
      (node (ref "C97") (pin "1") (pinfunction "1_1") (pintype "passive"))
      (node (ref "C98") (pin "1") (pinfunction "1_1") (pintype "passive"))
      (node (ref "C99") (pin "1") (pinfunction "1_1") (pintype "passive"))
      (node (ref "J12") (pin "3") (pinfunction "3_3") (pintype "passive"))
      (node (ref "J8") (pin "A1") (pinfunction "GND1_A1") (pintype "passive"))
      (node (ref "J8") (pin "A12") (pinfunction "GND2_A12") (pintype "passive"))
      (node (ref "J8") (pin "B1") (pinfunction "GND3_B1") (pintype "passive"))
      (node (ref "J8") (pin "B12") (pinfunction "GND4_B12") (pintype "passive"))
      (node (ref "J8") (pin "SH1") (pinfunction "SHIELD1_SH1") (pintype "passive"))
      (node (ref "J8") (pin "SH2") (pinfunction "SHIELD2_SH2") (pintype "passive"))
      (node (ref "J8") (pin "SH3") (pinfunction "SHIELD3_SH3") (pintype "passive"))
      (node (ref "J8") (pin "SH4") (pinfunction "SHIELD4_SH4") (pintype "passive"))
      (node (ref "JP1") (pin "2") (pinfunction "2_2") (pintype "passive"))
      (node (ref "JP2") (pin "2") (pinfunction "2_2") (pintype "passive"))
      (node (ref "L24") (pin "1") (pinfunction "1_1") (pintype "passive"))
      (node (ref "R104") (pin "1") (pinfunction "1_1") (pintype "passive"))
      (node (ref "R105") (pin "1") (pinfunction "1_1") (pintype "passive"))
      (node (ref "R106") (pin "1") (pinfunction "1_1") (pintype "passive"))
      (node (ref "R108") (pin "1") (pinfunction "1_1") (pintype "passive"))
      (node (ref "U24") (pin "1") (pinfunction "GND-1_1") (pintype "passive"))
      (node (ref "U24") (pin "2") (pinfunction "GND_2") (pintype "passive"))
      (node (ref "U24") (pin "3") (pinfunction "GND-2_3") (pintype "passive"))
      (node (ref "U24") (pin "7") (pinfunction "GND-3_7") (pintype "passive"))
      (node (ref "U25") (pin "10") (pinfunction "~{I2Cs_IRQ}_10") (pintype "passive"))
      (node (ref "U25") (pin "11") (pinfunction "GND_11") (pintype "passive"))
      (node (ref "U25") (pin "12") (pinfunction "GND_12") (pintype "passive"))
      (node (ref "U25") (pin "14") (pinfunction "GND_14") (pintype "passive"))
      (node (ref "U25") (pin "18") (pinfunction "~{I2Cm_IRQ}_18") (pintype "input"))
      (node (ref "U25") (pin "31") (pinfunction "GND_31") (pintype "passive"))
      (node (ref "U25") (pin "39") (pinfunction "GND_PAD_39") (pintype "passive"))
      (node (ref "U26") (pin "4") (pinfunction "GND_4") (pintype "passive"))
      (node (ref "U27") (pin "27") (pinfunction "GND_27") (pintype "power_in"))
    )
    (net (code "22") (name "Net-(JP3-Pad2)") (class "Default")
      (node (ref "JP3") (pin "2") (pinfunction "2_2") (pintype "passive"))
      (node (ref "R117") (pin "2") (pinfunction "2_2") (pintype "passive"))
    )
    (net (code "23") (name "Net-(U25-DRAIN_PAD)") (class "Default")
      (node (ref "U25") (pin "15") (pinfunction "DRAIN_15") (pintype "passive"))
      (node (ref "U25") (pin "30") (pinfunction "DRAIN_30") (pintype "passive"))
      (node (ref "U25") (pin "40") (pinfunction "DRAIN_PAD_40") (pintype "passive"))
    )
    (net (code "24") (name "Net-(U26-A0)") (class "Default")
      (node (ref "R104") (pin "2") (pinfunction "2_2") (pintype "passive"))
      (node (ref "U26") (pin "1") (pinfunction "A0_1") (pintype "passive"))
    )
    (net (code "25") (name "Net-(U26-A1)") (class "Default")
      (node (ref "R105") (pin "2") (pinfunction "2_2") (pintype "passive"))
      (node (ref "U26") (pin "2") (pinfunction "A1_2") (pintype "passive"))
    )
    (net (code "26") (name "Net-(U26-A2)") (class "Default")
      (node (ref "R106") (pin "2") (pinfunction "2_2") (pintype "passive"))
      (node (ref "U26") (pin "3") (pinfunction "A2_3") (pintype "passive"))
    )
    (net (code "27") (name "Net-(U26-WP)") (class "Default")
      (node (ref "R108") (pin "2") (pinfunction "2_2") (pintype "passive"))
      (node (ref "U26") (pin "7") (pinfunction "WP_7") (pintype "passive"))
    )
    (net (code "28") (name "Net-(U27-BATP)") (class "Default")
      (node (ref "R111") (pin "2") (pinfunction "2_2") (pintype "passive"))
      (node (ref "U27") (pin "18") (pinfunction "BATP_18") (pintype "passive"))
    )
    (net (code "29") (name "Net-(U27-BTST1)") (class "Default")
      (node (ref "C104") (pin "1") (pinfunction "1_1") (pintype "passive"))
      (node (ref "U27") (pin "4") (pinfunction "BTST1_4") (pintype "passive"))
    )
    (net (code "30") (name "Net-(U27-BTST2)") (class "Default")
      (node (ref "C105") (pin "1") (pinfunction "1_1") (pintype "passive"))
      (node (ref "U27") (pin "19") (pinfunction "BTST2_19") (pintype "passive"))
    )
    (net (code "31") (name "Net-(U27-SDRV)") (class "Default")
      (node (ref "C115") (pin "2") (pinfunction "2_2") (pintype "passive"))
      (node (ref "U27") (pin "24") (pinfunction "SDRV_24") (pintype "passive"))
    )
    (net (code "32") (name "Net-(U27-SW1)") (class "Default")
      (node (ref "C104") (pin "2") (pinfunction "2_2") (pintype "passive"))
      (node (ref "L16") (pin "1") (pinfunction "1_1") (pintype "passive"))
      (node (ref "U27") (pin "28") (pinfunction "SW1_28") (pintype "passive"))
    )
    (net (code "33") (name "Net-(U27-SW2)") (class "Default")
      (node (ref "C105") (pin "2") (pinfunction "2_2") (pintype "passive"))
      (node (ref "L16") (pin "2") (pinfunction "2_2") (pintype "passive"))
      (node (ref "U27") (pin "26") (pinfunction "SW2_26") (pintype "passive"))
    )
    (net (code "34") (name "P3V3") (class "Default")
      (node (ref "C87") (pin "2") (pinfunction "2_2") (pintype "passive"))
      (node (ref "U25") (pin "38") (pinfunction "VIN_3V3_38") (pintype "power_in"))
    )
    (net (code "35") (name "PACK+") (class "Default")
      (node (ref "C112") (pin "2") (pinfunction "2_2") (pintype "passive"))
      (node (ref "C113") (pin "2") (pinfunction "2_2") (pintype "passive"))
      (node (ref "C114") (pin "2") (pinfunction "2_2") (pintype "passive"))
      (node (ref "JP2") (pin "1") (pinfunction "1_1") (pintype "passive"))
      (node (ref "R111") (pin "1") (pinfunction "1_1") (pintype "passive"))
      (node (ref "U27") (pin "22") (pinfunction "BAT_22") (pintype "passive"))
      (node (ref "U27") (pin "23") (pinfunction "BAT_23") (pintype "passive"))
    )
    (net (code "36") (name "PP5V") (class "Default")
      (node (ref "U25") (pin "34") (pinfunction "PP5V_34") (pintype "power_in"))
      (node (ref "U25") (pin "35") (pinfunction "PP5V_35") (pintype "power_in"))
    )
    (net (code "37") (name "VCC_SYS") (class "Default")
      (node (ref "C106") (pin "2") (pinfunction "2_2") (pintype "passive"))
      (node (ref "C107") (pin "2") (pinfunction "2_2") (pintype "passive"))
      (node (ref "C108") (pin "2") (pinfunction "2_2") (pintype "passive"))
      (node (ref "C109") (pin "2") (pinfunction "2_2") (pintype "passive"))
      (node (ref "C110") (pin "2") (pinfunction "2_2") (pintype "passive"))
      (node (ref "C111") (pin "2") (pinfunction "2_2") (pintype "passive"))
      (node (ref "JP1") (pin "1") (pinfunction "1_1") (pintype "passive"))
      (node (ref "U27") (pin "25") (pinfunction "SYS_25") (pintype "passive"))
    )
    (net (code "38") (name "unconnected-(J8-RX1+-PadB11)") (class "Default")
      (node (ref "J8") (pin "B11") (pinfunction "RX1+_B11") (pintype "input+no_connect"))
    )
    (net (code "39") (name "unconnected-(J8-RX1--PadB10)") (class "Default")
      (node (ref "J8") (pin "B10") (pinfunction "RX1-_B10") (pintype "input+no_connect"))
    )
    (net (code "40") (name "unconnected-(J8-RX2+-PadA11)") (class "Default")
      (node (ref "J8") (pin "A11") (pinfunction "RX2+_A11") (pintype "input+no_connect"))
    )
    (net (code "41") (name "unconnected-(J8-RX2--PadA10)") (class "Default")
      (node (ref "J8") (pin "A10") (pinfunction "RX2-_A10") (pintype "input+no_connect"))
    )
    (net (code "42") (name "unconnected-(J8-SBU1-PadA8)") (class "Default")
      (node (ref "J8") (pin "A8") (pinfunction "SBU1_A8") (pintype "bidirectional+no_connect"))
    )
    (net (code "43") (name "unconnected-(J8-SBU2-PadB8)") (class "Default")
      (node (ref "J8") (pin "B8") (pinfunction "SBU2_B8") (pintype "bidirectional+no_connect"))
    )
    (net (code "44") (name "unconnected-(J8-TX1+-PadA2)") (class "Default")
      (node (ref "J8") (pin "A2") (pinfunction "TX1+_A2") (pintype "output+no_connect"))
    )
    (net (code "45") (name "unconnected-(J8-TX1--PadA3)") (class "Default")
      (node (ref "J8") (pin "A3") (pinfunction "TX1-_A3") (pintype "output+no_connect"))
    )
    (net (code "46") (name "unconnected-(J8-TX2+-PadB2)") (class "Default")
      (node (ref "J8") (pin "B2") (pinfunction "TX2+_B2") (pintype "output+no_connect"))
    )
    (net (code "47") (name "unconnected-(J8-TX2--PadB3)") (class "Default")
      (node (ref "J8") (pin "B3") (pinfunction "TX2-_B3") (pintype "output+no_connect"))
    )
    (net (code "48") (name "unconnected-(U25-GPIO0-Pad5)") (class "Default")
      (node (ref "U25") (pin "5") (pinfunction "GPIO0_5") (pintype "bidirectional+no_connect"))
    )
    (net (code "49") (name "unconnected-(U25-GPIO1-Pad6)") (class "Default")
      (node (ref "U25") (pin "6") (pinfunction "GPIO1_6") (pintype "bidirectional+no_connect"))
    )
    (net (code "50") (name "unconnected-(U25-GPIO2-Pad7)") (class "Default")
      (node (ref "U25") (pin "7") (pinfunction "GPIO2_7") (pintype "bidirectional+no_connect"))
    )
    (net (code "51") (name "unconnected-(U25-GPIO3-Pad19)") (class "Default")
      (node (ref "U25") (pin "19") (pinfunction "GPIO3_19") (pintype "bidirectional+no_connect"))
    )
    (net (code "52") (name "unconnected-(U25-GPIO6-Pad37)") (class "Default")
      (node (ref "U25") (pin "37") (pinfunction "GPIO6_37") (pintype "bidirectional+no_connect"))
    )
    (net (code "53") (name "unconnected-(U25-GPIO7-Pad36)") (class "Default")
      (node (ref "U25") (pin "36") (pinfunction "GPIO7_36") (pintype "bidirectional+no_connect"))
    )
    (net (code "54") (name "unconnected-(U25-GPIO11-Pad13)") (class "Default")
      (node (ref "U25") (pin "13") (pinfunction "GPIO11_13") (pintype "bidirectional+no_connect"))
    )
    (net (code "55") (name "unconnected-(U27-D+-Pad6)") (class "Default")
      (node (ref "U27") (pin "6") (pinfunction "D+_6") (pintype "bidirectional+no_connect"))
    )
    (net (code "56") (name "unconnected-(U27-D--Pad7)") (class "Default")
      (node (ref "U27") (pin "7") (pinfunction "D-_7") (pintype "bidirectional+no_connect"))
    )
    (net (code "57") (name "unconnected-(U27-~{INT}-Pad21)") (class "Default")
      (node (ref "U27") (pin "21") (pinfunction "~{INT}_21") (pintype "passive"))
    )
    (net (code "58") (name "unconnected-(U27-~{QON}-Pad12)") (class "Default")
      (node (ref "U27") (pin "12") (pinfunction "~{QON}_12") (pintype "passive+no_connect"))
    )
  )
)
